# MCU.net
KiCad netlist of a schematic drawn in Altium Designer
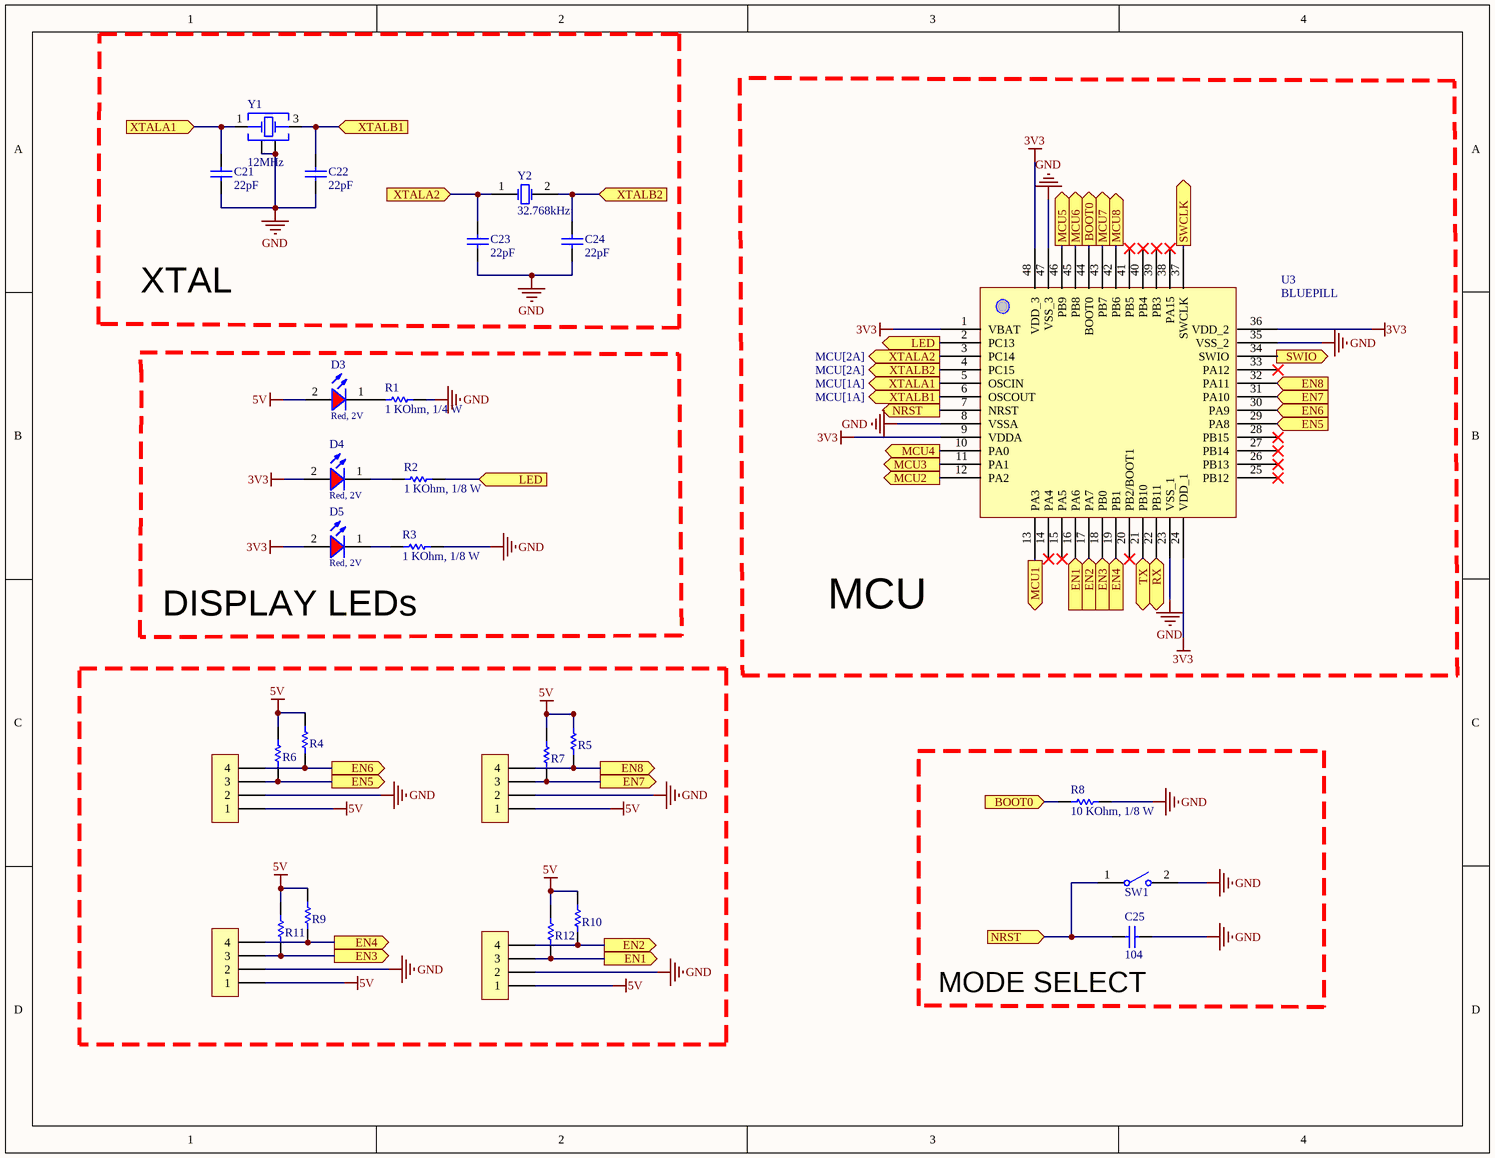
[diagram p0: MCU.SchDoc]

(export (version "E")
  (design (tool "Eeschema 10.0.6"))
  (components
    (comp (ref "C21")
      (value "22pF")
      (footprint "tu 0603")
      (description "Dán")
      (libsource (lib "Capacitor") (part "Tu 0603 22pF 50V 10%"))
    )
    (comp (ref "C22")
      (value "22pF")
      (footprint "tu 0603")
      (description "Dán")
      (libsource (lib "Capacitor") (part "Tu 0603 22pF 50V 10%"))
    )
    (comp (ref "C23")
      (value "22pF")
      (footprint "tu 0603")
      (description "Dán")
      (libsource (lib "Capacitor") (part "Tu 0603 22pF 50V 10%"))
    )
    (comp (ref "C24")
      (value "22pF")
      (footprint "tu 0603")
      (description "Dán")
      (libsource (lib "Capacitor") (part "Tu 0603 22pF 50V 10%"))
    )
    (comp (ref "C25")
      (value "104")
      (footprint "tu 0805")
      (description "Dán")
      (libsource (lib "Capacitor") (part "Tu 0805 104 50V 10%"))
    )
    (comp (ref "D3")
      (value "Red, 2V")
      (footprint "WL-SMCW_0603_H=0.7mm")
      (description "WL-SMCW SMT Mono-color Chip LED Waterclear, size 0603, Red, 2V, 140deg")
      (libsource (lib "Altium_LED") (part "160603RedClear"))
    )
    (comp (ref "D4")
      (value "Red, 2V")
      (footprint "WL-SMCW_0603_H=0.7mm")
      (description "WL-SMCW SMT Mono-color Chip LED Blur, size 0603, Red, 2V, 140deg")
      (libsource (lib "Altium_LED") (part "160603RedBlur"))
    )
    (comp (ref "D5")
      (value "Red, 2V")
      (footprint "WL-SMCW_0603_H=0.7mm")
      (description "WL-SMCW SMT Mono-color Chip LED Blur, size 0603, Red, 2V, 140deg")
      (libsource (lib "Altium_LED") (part "160603RedBlur"))
    )
    (comp (ref "H1")
      (value "Header 4P 2.54 Duc Cong")
      (footprint "Header 4P DC 2.54")
      (description "Cắm")
      (libsource (lib "Header") (part "Header 4P 2.54 Duc Cong"))
    )
    (comp (ref "H2")
      (value "Header 4P 2.54 Duc Cong")
      (footprint "Header 4P DC 2.54")
      (description "Cắm")
      (libsource (lib "Header") (part "Header 4P 2.54 Duc Cong"))
    )
    (comp (ref "H3")
      (value "Header 4P 2.54 Duc Cong")
      (footprint "Header 4P DC 2.54")
      (description "Cắm")
      (libsource (lib "Header") (part "Header 4P 2.54 Duc Cong"))
    )
    (comp (ref "H4")
      (value "Header 4P 2.54 Duc Cong")
      (footprint "Header 4P DC 2.54")
      (description "Cắm")
      (libsource (lib "Header") (part "Header 4P 2.54 Duc Cong"))
    )
    (comp (ref "R1")
      (value "1 KOhm, 1/4 W")
      (footprint "resistor_0603")
      (description "RES, size 0603, 1 KOhm, 1/4 W")
      (libsource (lib "Altium_Resistor") (part "0006031021"))
    )
    (comp (ref "R2")
      (value "1 KOhm, 1/8 W")
      (footprint "RESISTOR_0805")
      (description "RES, size 0805, 1 KOhm, 1/8 W")
      (libsource (lib "Altium_Resistor") (part "0008051025"))
    )
    (comp (ref "R3")
      (value "1 KOhm, 1/8 W")
      (footprint "RESISTOR_0805")
      (description "RES, size 0805, 1 KOhm, 1/8 W")
      (libsource (lib "Altium_Resistor") (part "0008051025"))
    )
    (comp (ref "R4")
      (value "1 KOhm, 1/8 W")
      (footprint "RESISTOR_0805")
      (description "RES, size 0805, 1 KOhm, 1/8 W")
      (libsource (lib "Altium_Resistor") (part "0008051025"))
    )
    (comp (ref "R5")
      (value "1 KOhm, 1/8 W")
      (footprint "RESISTOR_0805")
      (description "RES, size 0805, 1 KOhm, 1/8 W")
      (libsource (lib "Altium_Resistor") (part "0008051025"))
    )
    (comp (ref "R6")
      (value "1 KOhm, 1/8 W")
      (footprint "RESISTOR_0805")
      (description "RES, size 0805, 1 KOhm, 1/8 W")
      (libsource (lib "Altium_Resistor") (part "0008051025"))
    )
    (comp (ref "R7")
      (value "1 KOhm, 1/8 W")
      (footprint "RESISTOR_0805")
      (description "RES, size 0805, 1 KOhm, 1/8 W")
      (libsource (lib "Altium_Resistor") (part "0008051025"))
    )
    (comp (ref "R8")
      (value "10 KOhm, 1/8 W")
      (footprint "RESISTOR_0805")
      (description "RES, size 0805, 10 KOhm, 1/8 W")
      (libsource (lib "Altium_Resistor") (part "0008051035"))
    )
    (comp (ref "R9")
      (value "1 KOhm, 1/8 W")
      (footprint "RESISTOR_0805")
      (description "RES, size 0805, 1 KOhm, 1/8 W")
      (libsource (lib "Altium_Resistor") (part "0008051025"))
    )
    (comp (ref "R10")
      (value "1 KOhm, 1/8 W")
      (footprint "RESISTOR_0805")
      (description "RES, size 0805, 1 KOhm, 1/8 W")
      (libsource (lib "Altium_Resistor") (part "0008051025"))
    )
    (comp (ref "R11")
      (value "1 KOhm, 1/8 W")
      (footprint "RESISTOR_0805")
      (description "RES, size 0805, 1 KOhm, 1/8 W")
      (libsource (lib "Altium_Resistor") (part "0008051025"))
    )
    (comp (ref "R12")
      (value "1 KOhm, 1/8 W")
      (footprint "RESISTOR_0805")
      (description "RES, size 0805, 1 KOhm, 1/8 W")
      (libsource (lib "Altium_Resistor") (part "0008051025"))
    )
    (comp (ref "SW1")
      (value "434111050826")
      (footprint "WS-TASV_L6W3.5H5_4341x10508x6")
      (description "WS-TASV SMT Tact Switch, L6 x W3.5 x H5mm, 260g, SPST-NO, 12V, 50mA")
      (fields (field (name "MANUFACTURER") "Wurth Elektronik"))
      (libsource (lib "Altium_Button") (part "434111050826"))
    )
    (comp (ref "U3")
      (value "BLUEPILL")
      (footprint "STM32F103C8T6")
      (libsource (lib "STM32F103C8T6_Library") (part "STM32F103C8T6"))
    )
    (comp (ref "Y1")
      (value "12MHz")
      (footprint "WE-XTAL_CFPX-180")
      (description "WE-XTAL Quartz Crystal, SMT, CFPX-180, 12MHz, +/-30ppm")
      (fields
        (field (name "MANUFACTURER PART NUMBER") "NX3225SA-12MHZ-STD-CSR-6")
        (field (name "MANUFACTURER") "NDK")
      )
      (libsource (lib "Altium_XTAL_3525") (part "073525126010"))
    )
    (comp (ref "Y2")
      (value "32.768kHz")
      (footprint "WE-XTAL_WATCH_830014219B")
      (description "WE-XTAL Watch Crystal, THT, WATCH, 32.768kHz, +/-20ppm")
      (fields
        (field (name "MANUFACTURER PART NUMBER") "830014219B")
        (field (name "MANUFACTURER") "Wurth Elektronik")
      )
      (libsource (lib "Altium_XTAL_WATCH") (part "070002323006"))
    )
  )
  (nets
    (net (code "1") (name "/BOOT0") (class "Default")
      (node (ref "R8") (pin "1") (pinfunction "1_1") (pintype "passive"))
      (node (ref "U3") (pin "44") (pinfunction "BOOT0_44") (pintype "passive"))
    )
    (net (code "2") (name "/EN1") (class "Default")
      (node (ref "H4") (pin "3") (pinfunction "3_3") (pintype "passive"))
      (node (ref "R12") (pin "1") (pinfunction "1_1") (pintype "passive"))
      (node (ref "U3") (pin "16") (pinfunction "PA6_16") (pintype "passive"))
    )
    (net (code "3") (name "/EN2") (class "Default")
      (node (ref "H4") (pin "4") (pinfunction "4_4") (pintype "passive"))
      (node (ref "R10") (pin "1") (pinfunction "1_1") (pintype "passive"))
      (node (ref "U3") (pin "17") (pinfunction "PA7_17") (pintype "passive"))
    )
    (net (code "4") (name "/EN3") (class "Default")
      (node (ref "H3") (pin "3") (pinfunction "3_3") (pintype "passive"))
      (node (ref "R11") (pin "1") (pinfunction "1_1") (pintype "passive"))
      (node (ref "U3") (pin "18") (pinfunction "PB0_18") (pintype "passive"))
    )
    (net (code "5") (name "/EN4") (class "Default")
      (node (ref "H3") (pin "4") (pinfunction "4_4") (pintype "passive"))
      (node (ref "R9") (pin "1") (pinfunction "1_1") (pintype "passive"))
      (node (ref "U3") (pin "19") (pinfunction "PB1_19") (pintype "passive"))
    )
    (net (code "6") (name "/EN5") (class "Default")
      (node (ref "H1") (pin "3") (pinfunction "3_3") (pintype "passive"))
      (node (ref "R6") (pin "1") (pinfunction "1_1") (pintype "passive"))
      (node (ref "U3") (pin "29") (pinfunction "PA8_29") (pintype "passive"))
    )
    (net (code "7") (name "/EN6") (class "Default")
      (node (ref "H1") (pin "4") (pinfunction "4_4") (pintype "passive"))
      (node (ref "R4") (pin "1") (pinfunction "1_1") (pintype "passive"))
      (node (ref "U3") (pin "30") (pinfunction "PA9_30") (pintype "passive"))
    )
    (net (code "8") (name "/EN7") (class "Default")
      (node (ref "H2") (pin "3") (pinfunction "3_3") (pintype "passive"))
      (node (ref "R7") (pin "1") (pinfunction "1_1") (pintype "passive"))
      (node (ref "U3") (pin "31") (pinfunction "PA10_31") (pintype "passive"))
    )
    (net (code "9") (name "/EN8") (class "Default")
      (node (ref "H2") (pin "4") (pinfunction "4_4") (pintype "passive"))
      (node (ref "R5") (pin "1") (pinfunction "1_1") (pintype "passive"))
      (node (ref "U3") (pin "32") (pinfunction "PA11_32") (pintype "passive"))
    )
    (net (code "10") (name "/LED") (class "Default")
      (node (ref "R2") (pin "2") (pinfunction "2_2") (pintype "passive"))
      (node (ref "U3") (pin "2") (pinfunction "PC13_2") (pintype "passive"))
    )
    (net (code "11") (name "/MCU1") (class "Default")
      (node (ref "U3") (pin "13") (pinfunction "PA3_13") (pintype "passive"))
    )
    (net (code "12") (name "/MCU2") (class "Default")
      (node (ref "U3") (pin "12") (pinfunction "PA2_12") (pintype "passive"))
    )
    (net (code "13") (name "/MCU3") (class "Default")
      (node (ref "U3") (pin "11") (pinfunction "PA1_11") (pintype "passive"))
    )
    (net (code "14") (name "/MCU4") (class "Default")
      (node (ref "U3") (pin "10") (pinfunction "PA0_10") (pintype "passive"))
    )
    (net (code "15") (name "/MCU5") (class "Default")
      (node (ref "U3") (pin "46") (pinfunction "PB9_46") (pintype "passive"))
    )
    (net (code "16") (name "/MCU6") (class "Default")
      (node (ref "U3") (pin "45") (pinfunction "PB8_45") (pintype "passive"))
    )
    (net (code "17") (name "/MCU7") (class "Default")
      (node (ref "U3") (pin "43") (pinfunction "PB7_43") (pintype "passive"))
    )
    (net (code "18") (name "/MCU8") (class "Default")
      (node (ref "U3") (pin "42") (pinfunction "PB6_42") (pintype "passive"))
    )
    (net (code "19") (name "/NRST") (class "Default")
      (node (ref "C25") (pin "1") (pinfunction "1_1") (pintype "passive"))
      (node (ref "SW1") (pin "1") (pinfunction "1_1") (pintype "passive"))
      (node (ref "U3") (pin "7") (pinfunction "NRST_7") (pintype "passive"))
    )
    (net (code "20") (name "/RX") (class "Default")
      (node (ref "U3") (pin "22") (pinfunction "PB11_22") (pintype "passive"))
    )
    (net (code "21") (name "/SWCLK") (class "Default")
      (node (ref "U3") (pin "37") (pinfunction "SWCLK_37") (pintype "passive"))
    )
    (net (code "22") (name "/SWIO") (class "Default")
      (node (ref "U3") (pin "34") (pinfunction "SWIO_34") (pintype "passive"))
    )
    (net (code "23") (name "/TX") (class "Default")
      (node (ref "U3") (pin "21") (pinfunction "PB10_21") (pintype "passive"))
    )
    (net (code "24") (name "/XTALA1") (class "Default")
      (node (ref "C21") (pin "2") (pinfunction "2_2") (pintype "passive"))
      (node (ref "U3") (pin "5") (pinfunction "OSCIN_5") (pintype "passive"))
      (node (ref "Y1") (pin "1") (pinfunction "Crystal_1") (pintype "passive"))
    )
    (net (code "25") (name "/XTALA2") (class "Default")
      (node (ref "C23") (pin "1") (pinfunction "1_1") (pintype "passive"))
      (node (ref "U3") (pin "3") (pinfunction "PC14_3") (pintype "passive"))
      (node (ref "Y2") (pin "1") (pinfunction "OSC1_1") (pintype "passive"))
    )
    (net (code "26") (name "/XTALB1") (class "Default")
      (node (ref "C22") (pin "1") (pinfunction "1_1") (pintype "passive"))
      (node (ref "U3") (pin "6") (pinfunction "OSCOUT_6") (pintype "passive"))
      (node (ref "Y1") (pin "3") (pinfunction "Crystal_3") (pintype "passive"))
    )
    (net (code "27") (name "/XTALB2") (class "Default")
      (node (ref "C24") (pin "1") (pinfunction "1_1") (pintype "passive"))
      (node (ref "U3") (pin "4") (pinfunction "PC15_4") (pintype "passive"))
      (node (ref "Y2") (pin "2") (pinfunction "OSC2_2") (pintype "passive"))
    )
    (net (code "28") (name "3V3") (class "Default")
      (node (ref "D4") (pin "2") (pinfunction "A_2") (pintype "passive"))
      (node (ref "D5") (pin "2") (pinfunction "A_2") (pintype "passive"))
      (node (ref "U3") (pin "1") (pinfunction "VBAT_1") (pintype "passive"))
      (node (ref "U3") (pin "24") (pinfunction "VDD_1_24") (pintype "passive"))
      (node (ref "U3") (pin "36") (pinfunction "VDD_2_36") (pintype "passive"))
      (node (ref "U3") (pin "48") (pinfunction "VDD_3_48") (pintype "passive"))
      (node (ref "U3") (pin "9") (pinfunction "VDDA_9") (pintype "passive"))
    )
    (net (code "29") (name "5V") (class "Default")
      (node (ref "D3") (pin "2") (pinfunction "A_2") (pintype "passive"))
      (node (ref "H1") (pin "1") (pinfunction "1_1") (pintype "passive"))
      (node (ref "H2") (pin "1") (pinfunction "1_1") (pintype "passive"))
      (node (ref "H3") (pin "1") (pinfunction "1_1") (pintype "passive"))
      (node (ref "H4") (pin "1") (pinfunction "1_1") (pintype "passive"))
      (node (ref "R10") (pin "2") (pinfunction "2_2") (pintype "passive"))
      (node (ref "R11") (pin "2") (pinfunction "2_2") (pintype "passive"))
      (node (ref "R12") (pin "2") (pinfunction "2_2") (pintype "passive"))
      (node (ref "R4") (pin "2") (pinfunction "2_2") (pintype "passive"))
      (node (ref "R5") (pin "2") (pinfunction "2_2") (pintype "passive"))
      (node (ref "R6") (pin "2") (pinfunction "2_2") (pintype "passive"))
      (node (ref "R7") (pin "2") (pinfunction "2_2") (pintype "passive"))
      (node (ref "R9") (pin "2") (pinfunction "2_2") (pintype "passive"))
    )
    (net (code "30") (name "GND") (class "Default")
      (node (ref "C21") (pin "1") (pinfunction "1_1") (pintype "passive"))
      (node (ref "C22") (pin "2") (pinfunction "2_2") (pintype "passive"))
      (node (ref "C23") (pin "2") (pinfunction "2_2") (pintype "passive"))
      (node (ref "C24") (pin "2") (pinfunction "2_2") (pintype "passive"))
      (node (ref "C25") (pin "2") (pinfunction "2_2") (pintype "passive"))
      (node (ref "H1") (pin "2") (pinfunction "2_2") (pintype "passive"))
      (node (ref "H2") (pin "2") (pinfunction "2_2") (pintype "passive"))
      (node (ref "H3") (pin "2") (pinfunction "2_2") (pintype "passive"))
      (node (ref "H4") (pin "2") (pinfunction "2_2") (pintype "passive"))
      (node (ref "R1") (pin "2") (pinfunction "2_2") (pintype "passive"))
      (node (ref "R3") (pin "2") (pinfunction "2_2") (pintype "passive"))
      (node (ref "R8") (pin "2") (pinfunction "2_2") (pintype "passive"))
      (node (ref "SW1") (pin "2") (pinfunction "2_2") (pintype "passive"))
      (node (ref "U3") (pin "23") (pinfunction "VSS_1_23") (pintype "passive"))
      (node (ref "U3") (pin "35") (pinfunction "VSS_2_35") (pintype "passive"))
      (node (ref "U3") (pin "47") (pinfunction "VSS_3_47") (pintype "passive"))
      (node (ref "U3") (pin "8") (pinfunction "VSSA_8") (pintype "passive"))
      (node (ref "Y1") (pin "2") (pinfunction "GND_2") (pintype "passive"))
      (node (ref "Y1") (pin "4") (pinfunction "GND_4") (pintype "passive"))
    )
    (net (code "31") (name "Net-(D3-K)") (class "Default")
      (node (ref "D3") (pin "1") (pinfunction "K_1") (pintype "passive"))
      (node (ref "R1") (pin "1") (pinfunction "1_1") (pintype "passive"))
    )
    (net (code "32") (name "Net-(D4-K)") (class "Default")
      (node (ref "D4") (pin "1") (pinfunction "K_1") (pintype "passive"))
      (node (ref "R2") (pin "1") (pinfunction "1_1") (pintype "passive"))
    )
    (net (code "33") (name "Net-(D5-K)") (class "Default")
      (node (ref "D5") (pin "1") (pinfunction "K_1") (pintype "passive"))
      (node (ref "R3") (pin "1") (pinfunction "1_1") (pintype "passive"))
    )
    (net (code "34") (name "unconnected-(U3-PA4-Pad14)") (class "Default")
      (node (ref "U3") (pin "14") (pinfunction "PA4_14") (pintype "passive+no_connect"))
    )
    (net (code "35") (name "unconnected-(U3-PA5-Pad15)") (class "Default")
      (node (ref "U3") (pin "15") (pinfunction "PA5_15") (pintype "passive+no_connect"))
    )
    (net (code "36") (name "unconnected-(U3-PA12-Pad33)") (class "Default")
      (node (ref "U3") (pin "33") (pinfunction "PA12_33") (pintype "passive+no_connect"))
    )
    (net (code "37") (name "unconnected-(U3-PA15-Pad38)") (class "Default")
      (node (ref "U3") (pin "38") (pinfunction "PA15_38") (pintype "passive+no_connect"))
    )
    (net (code "38") (name "unconnected-(U3-PB2{slash}BOOT1-Pad20)") (class "Default")
      (node (ref "U3") (pin "20") (pinfunction "PB2/BOOT1_20") (pintype "passive+no_connect"))
    )
    (net (code "39") (name "unconnected-(U3-PB3-Pad39)") (class "Default")
      (node (ref "U3") (pin "39") (pinfunction "PB3_39") (pintype "passive+no_connect"))
    )
    (net (code "40") (name "unconnected-(U3-PB4-Pad40)") (class "Default")
      (node (ref "U3") (pin "40") (pinfunction "PB4_40") (pintype "passive+no_connect"))
    )
    (net (code "41") (name "unconnected-(U3-PB5-Pad41)") (class "Default")
      (node (ref "U3") (pin "41") (pinfunction "PB5_41") (pintype "passive+no_connect"))
    )
    (net (code "42") (name "unconnected-(U3-PB12-Pad25)") (class "Default")
      (node (ref "U3") (pin "25") (pinfunction "PB12_25") (pintype "passive+no_connect"))
    )
    (net (code "43") (name "unconnected-(U3-PB13-Pad26)") (class "Default")
      (node (ref "U3") (pin "26") (pinfunction "PB13_26") (pintype "passive+no_connect"))
    )
    (net (code "44") (name "unconnected-(U3-PB14-Pad27)") (class "Default")
      (node (ref "U3") (pin "27") (pinfunction "PB14_27") (pintype "passive+no_connect"))
    )
    (net (code "45") (name "unconnected-(U3-PB15-Pad28)") (class "Default")
      (node (ref "U3") (pin "28") (pinfunction "PB15_28") (pintype "passive+no_connect"))
    )
  )
)
